# EXT_EXPANDER.net
KiCad netlist of a schematic drawn in EAGLE
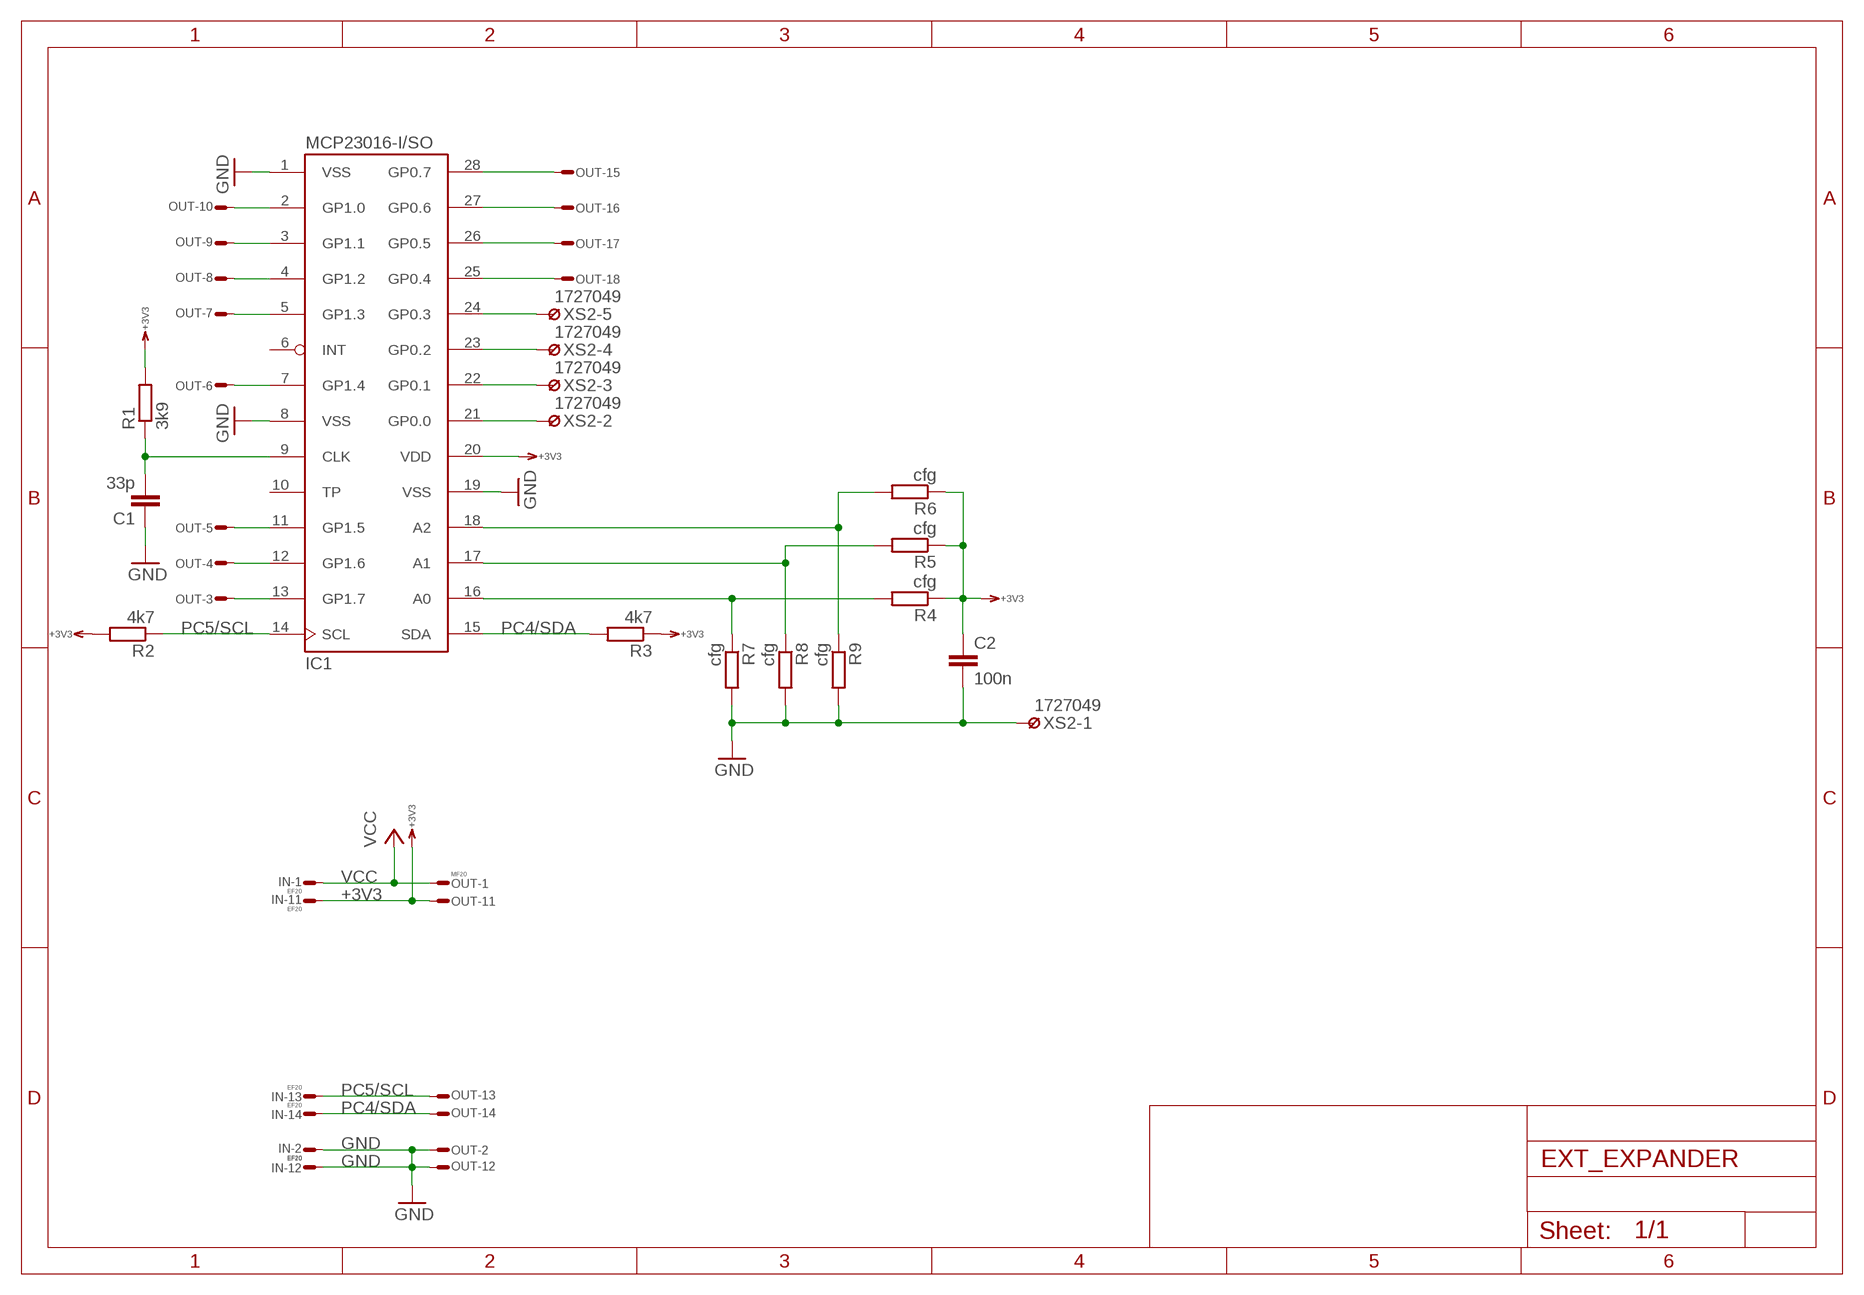
[diagram p0: schematic, sheet 1]

(export (version "E")
  (design (tool "Eeschema 10.0.6"))
  (components
    (comp (ref "C1")
      (value "33p")
      (footprint "eagle-import:0603")
      (libsource (lib "eagle-import") (part "C0603"))
    )
    (comp (ref "C2")
      (value "100n")
      (footprint "eagle-import:0603")
      (libsource (lib "eagle-import") (part "C0603"))
    )
    (comp (ref "IC1")
      (value "MCP23016-I/SO")
      (footprint "eagle-import:SOIC28")
      (libsource (lib "eagle-import") (part "MCP23016-I/SO"))
    )
    (comp (ref "IN")
      (value "EF20")
      (footprint "eagle-import:FE10-2WS")
      (libsource (lib "eagle-import") (part "FE20ELS"))
    )
    (comp (ref "OUT")
      (value "MF20")
      (footprint "eagle-import:ML20LS")
      (libsource (lib "eagle-import") (part "ML20?ELS"))
    )
    (comp (ref "R1")
      (value "3k9")
      (footprint "eagle-import:0603")
      (libsource (lib "eagle-import") (part "R0603"))
    )
    (comp (ref "R2")
      (value "4k7")
      (footprint "eagle-import:0603")
      (libsource (lib "eagle-import") (part "R0603"))
    )
    (comp (ref "R3")
      (value "4k7")
      (footprint "eagle-import:0603")
      (libsource (lib "eagle-import") (part "R0603"))
    )
    (comp (ref "R4")
      (value "cfg")
      (footprint "eagle-import:0603")
      (libsource (lib "eagle-import") (part "R0603"))
    )
    (comp (ref "R5")
      (value "cfg")
      (footprint "eagle-import:0603")
      (libsource (lib "eagle-import") (part "R0603"))
    )
    (comp (ref "R6")
      (value "cfg")
      (footprint "eagle-import:0603")
      (libsource (lib "eagle-import") (part "R0603"))
    )
    (comp (ref "R7")
      (value "cfg")
      (footprint "eagle-import:0603")
      (libsource (lib "eagle-import") (part "R0603"))
    )
    (comp (ref "R8")
      (value "cfg")
      (footprint "eagle-import:0603")
      (libsource (lib "eagle-import") (part "R0603"))
    )
    (comp (ref "R9")
      (value "cfg")
      (footprint "eagle-import:0603")
      (libsource (lib "eagle-import") (part "R0603"))
    )
    (comp (ref "XS2")
      (value "1727049")
      (footprint "eagle-import:1727049")
      (libsource (lib "eagle-import") (part "1727049"))
    )
  )
  (nets
    (net (code "1") (name "+3V3") (class "Default")
      (node (ref "C2") (pin "1") (pinfunction "1_1") (pintype "passive"))
      (node (ref "IC1") (pin "20") (pinfunction "VDD_20") (pintype "input"))
      (node (ref "IN") (pin "P$11") (pinfunction "S_P$11") (pintype "passive"))
      (node (ref "OUT") (pin "P$11") (pinfunction "S_P$11") (pintype "passive"))
      (node (ref "R1") (pin "2") (pinfunction "2_2") (pintype "passive"))
      (node (ref "R2") (pin "2") (pinfunction "2_2") (pintype "passive"))
      (node (ref "R3") (pin "1") (pinfunction "1_1") (pintype "passive"))
      (node (ref "R4") (pin "1") (pinfunction "1_1") (pintype "passive"))
      (node (ref "R5") (pin "1") (pinfunction "1_1") (pintype "passive"))
      (node (ref "R6") (pin "1") (pinfunction "1_1") (pintype "passive"))
    )
    (net (code "2") (name "/PC4{slash}SDA") (class "Default")
      (node (ref "IC1") (pin "15") (pinfunction "SDA_15") (pintype "bidirectional"))
      (node (ref "IN") (pin "P$14") (pinfunction "S_P$14") (pintype "passive"))
      (node (ref "OUT") (pin "P$14") (pinfunction "S_P$14") (pintype "passive"))
      (node (ref "R3") (pin "2") (pinfunction "2_2") (pintype "passive"))
    )
    (net (code "3") (name "/PC5{slash}SCL") (class "Default")
      (node (ref "IC1") (pin "14") (pinfunction "SCL_14") (pintype "input"))
      (node (ref "IN") (pin "P$13") (pinfunction "S_P$13") (pintype "passive"))
      (node (ref "OUT") (pin "P$13") (pinfunction "S_P$13") (pintype "passive"))
      (node (ref "R2") (pin "1") (pinfunction "1_1") (pintype "passive"))
    )
    (net (code "4") (name "GND") (class "Default")
      (node (ref "C1") (pin "1") (pinfunction "1_1") (pintype "passive"))
      (node (ref "C2") (pin "2") (pinfunction "2_2") (pintype "passive"))
      (node (ref "IC1") (pin "1") (pinfunction "VSS_1") (pintype "input"))
      (node (ref "IC1") (pin "19") (pinfunction "VSS_19") (pintype "input"))
      (node (ref "IC1") (pin "8") (pinfunction "VSS_8") (pintype "input"))
      (node (ref "IN") (pin "P$12") (pinfunction "S_P$12") (pintype "passive"))
      (node (ref "IN") (pin "P$2") (pinfunction "S_P$2") (pintype "passive"))
      (node (ref "OUT") (pin "P$12") (pinfunction "S_P$12") (pintype "passive"))
      (node (ref "OUT") (pin "P$2") (pinfunction "S_P$2") (pintype "passive"))
      (node (ref "R7") (pin "2") (pinfunction "2_2") (pintype "passive"))
      (node (ref "R8") (pin "2") (pinfunction "2_2") (pintype "passive"))
      (node (ref "R9") (pin "2") (pinfunction "2_2") (pintype "passive"))
      (node (ref "XS2") (pin "1") (pinfunction "K_1") (pintype "passive"))
    )
    (net (code "5") (name "Net-(IC1-A0)") (class "Default")
      (node (ref "IC1") (pin "16") (pinfunction "A0_16") (pintype "input"))
      (node (ref "R4") (pin "2") (pinfunction "2_2") (pintype "passive"))
      (node (ref "R7") (pin "1") (pinfunction "1_1") (pintype "passive"))
    )
    (net (code "6") (name "Net-(IC1-A1)") (class "Default")
      (node (ref "IC1") (pin "17") (pinfunction "A1_17") (pintype "input"))
      (node (ref "R5") (pin "2") (pinfunction "2_2") (pintype "passive"))
      (node (ref "R8") (pin "1") (pinfunction "1_1") (pintype "passive"))
    )
    (net (code "7") (name "Net-(IC1-A2)") (class "Default")
      (node (ref "IC1") (pin "18") (pinfunction "A2_18") (pintype "input"))
      (node (ref "R6") (pin "2") (pinfunction "2_2") (pintype "passive"))
      (node (ref "R9") (pin "1") (pinfunction "1_1") (pintype "passive"))
    )
    (net (code "8") (name "Net-(IC1-CLK)") (class "Default")
      (node (ref "C1") (pin "2") (pinfunction "2_2") (pintype "passive"))
      (node (ref "IC1") (pin "9") (pinfunction "CLK_9") (pintype "input"))
      (node (ref "R1") (pin "1") (pinfunction "1_1") (pintype "passive"))
    )
    (net (code "9") (name "Net-(IC1-GP0.0)") (class "Default")
      (node (ref "IC1") (pin "21") (pinfunction "GP0.0_21") (pintype "bidirectional"))
      (node (ref "XS2") (pin "2") (pinfunction "K_2") (pintype "passive"))
    )
    (net (code "10") (name "Net-(IC1-GP0.1)") (class "Default")
      (node (ref "IC1") (pin "22") (pinfunction "GP0.1_22") (pintype "bidirectional"))
      (node (ref "XS2") (pin "3") (pinfunction "K_3") (pintype "passive"))
    )
    (net (code "11") (name "Net-(IC1-GP0.2)") (class "Default")
      (node (ref "IC1") (pin "23") (pinfunction "GP0.2_23") (pintype "bidirectional"))
      (node (ref "XS2") (pin "4") (pinfunction "K_4") (pintype "passive"))
    )
    (net (code "12") (name "Net-(IC1-GP0.3)") (class "Default")
      (node (ref "IC1") (pin "24") (pinfunction "GP0.3_24") (pintype "bidirectional"))
      (node (ref "XS2") (pin "5") (pinfunction "K_5") (pintype "passive"))
    )
    (net (code "13") (name "Net-(IC1-GP0.4)") (class "Default")
      (node (ref "IC1") (pin "25") (pinfunction "GP0.4_25") (pintype "bidirectional"))
      (node (ref "OUT") (pin "P$18") (pinfunction "S_P$18") (pintype "passive"))
    )
    (net (code "14") (name "Net-(IC1-GP0.5)") (class "Default")
      (node (ref "IC1") (pin "26") (pinfunction "GP0.5_26") (pintype "bidirectional"))
      (node (ref "OUT") (pin "P$17") (pinfunction "S_P$17") (pintype "passive"))
    )
    (net (code "15") (name "Net-(IC1-GP0.6)") (class "Default")
      (node (ref "IC1") (pin "27") (pinfunction "GP0.6_27") (pintype "bidirectional"))
      (node (ref "OUT") (pin "P$16") (pinfunction "S_P$16") (pintype "passive"))
    )
    (net (code "16") (name "Net-(IC1-GP0.7)") (class "Default")
      (node (ref "IC1") (pin "28") (pinfunction "GP0.7_28") (pintype "bidirectional"))
      (node (ref "OUT") (pin "P$15") (pinfunction "S_P$15") (pintype "passive"))
    )
    (net (code "17") (name "Net-(IC1-GP1.0)") (class "Default")
      (node (ref "IC1") (pin "2") (pinfunction "GP1.0_2") (pintype "bidirectional"))
      (node (ref "OUT") (pin "P$10") (pinfunction "S_P$10") (pintype "passive"))
    )
    (net (code "18") (name "Net-(IC1-GP1.1)") (class "Default")
      (node (ref "IC1") (pin "3") (pinfunction "GP1.1_3") (pintype "bidirectional"))
      (node (ref "OUT") (pin "P$9") (pinfunction "S_P$9") (pintype "passive"))
    )
    (net (code "19") (name "Net-(IC1-GP1.2)") (class "Default")
      (node (ref "IC1") (pin "4") (pinfunction "GP1.2_4") (pintype "bidirectional"))
      (node (ref "OUT") (pin "P$8") (pinfunction "S_P$8") (pintype "passive"))
    )
    (net (code "20") (name "Net-(IC1-GP1.3)") (class "Default")
      (node (ref "IC1") (pin "5") (pinfunction "GP1.3_5") (pintype "bidirectional"))
      (node (ref "OUT") (pin "P$7") (pinfunction "S_P$7") (pintype "passive"))
    )
    (net (code "21") (name "Net-(IC1-GP1.4)") (class "Default")
      (node (ref "IC1") (pin "7") (pinfunction "GP1.4_7") (pintype "bidirectional"))
      (node (ref "OUT") (pin "P$6") (pinfunction "S_P$6") (pintype "passive"))
    )
    (net (code "22") (name "Net-(IC1-GP1.5)") (class "Default")
      (node (ref "IC1") (pin "11") (pinfunction "GP1.5_11") (pintype "bidirectional"))
      (node (ref "OUT") (pin "P$5") (pinfunction "S_P$5") (pintype "passive"))
    )
    (net (code "23") (name "Net-(IC1-GP1.6)") (class "Default")
      (node (ref "IC1") (pin "12") (pinfunction "GP1.6_12") (pintype "bidirectional"))
      (node (ref "OUT") (pin "P$4") (pinfunction "S_P$4") (pintype "passive"))
    )
    (net (code "24") (name "Net-(IC1-GP1.7)") (class "Default")
      (node (ref "IC1") (pin "13") (pinfunction "GP1.7_13") (pintype "bidirectional"))
      (node (ref "OUT") (pin "P$3") (pinfunction "S_P$3") (pintype "passive"))
    )
    (net (code "25") (name "VCC") (class "Default")
      (node (ref "IN") (pin "P$1") (pinfunction "S_P$1") (pintype "passive"))
      (node (ref "OUT") (pin "P$1") (pinfunction "S_P$1") (pintype "passive"))
    )
    (net (code "26") (name "unconnected-(IC1-INT-Pad6)") (class "Default")
      (node (ref "IC1") (pin "6") (pinfunction "INT_6") (pintype "output"))
    )
    (net (code "27") (name "unconnected-(IC1-TP-Pad10)") (class "Default")
      (node (ref "IC1") (pin "10") (pinfunction "TP_10") (pintype "bidirectional"))
    )
  )
)
